# arduino_pir_sensor.net
KiCad netlist of a schematic drawn in EAGLE
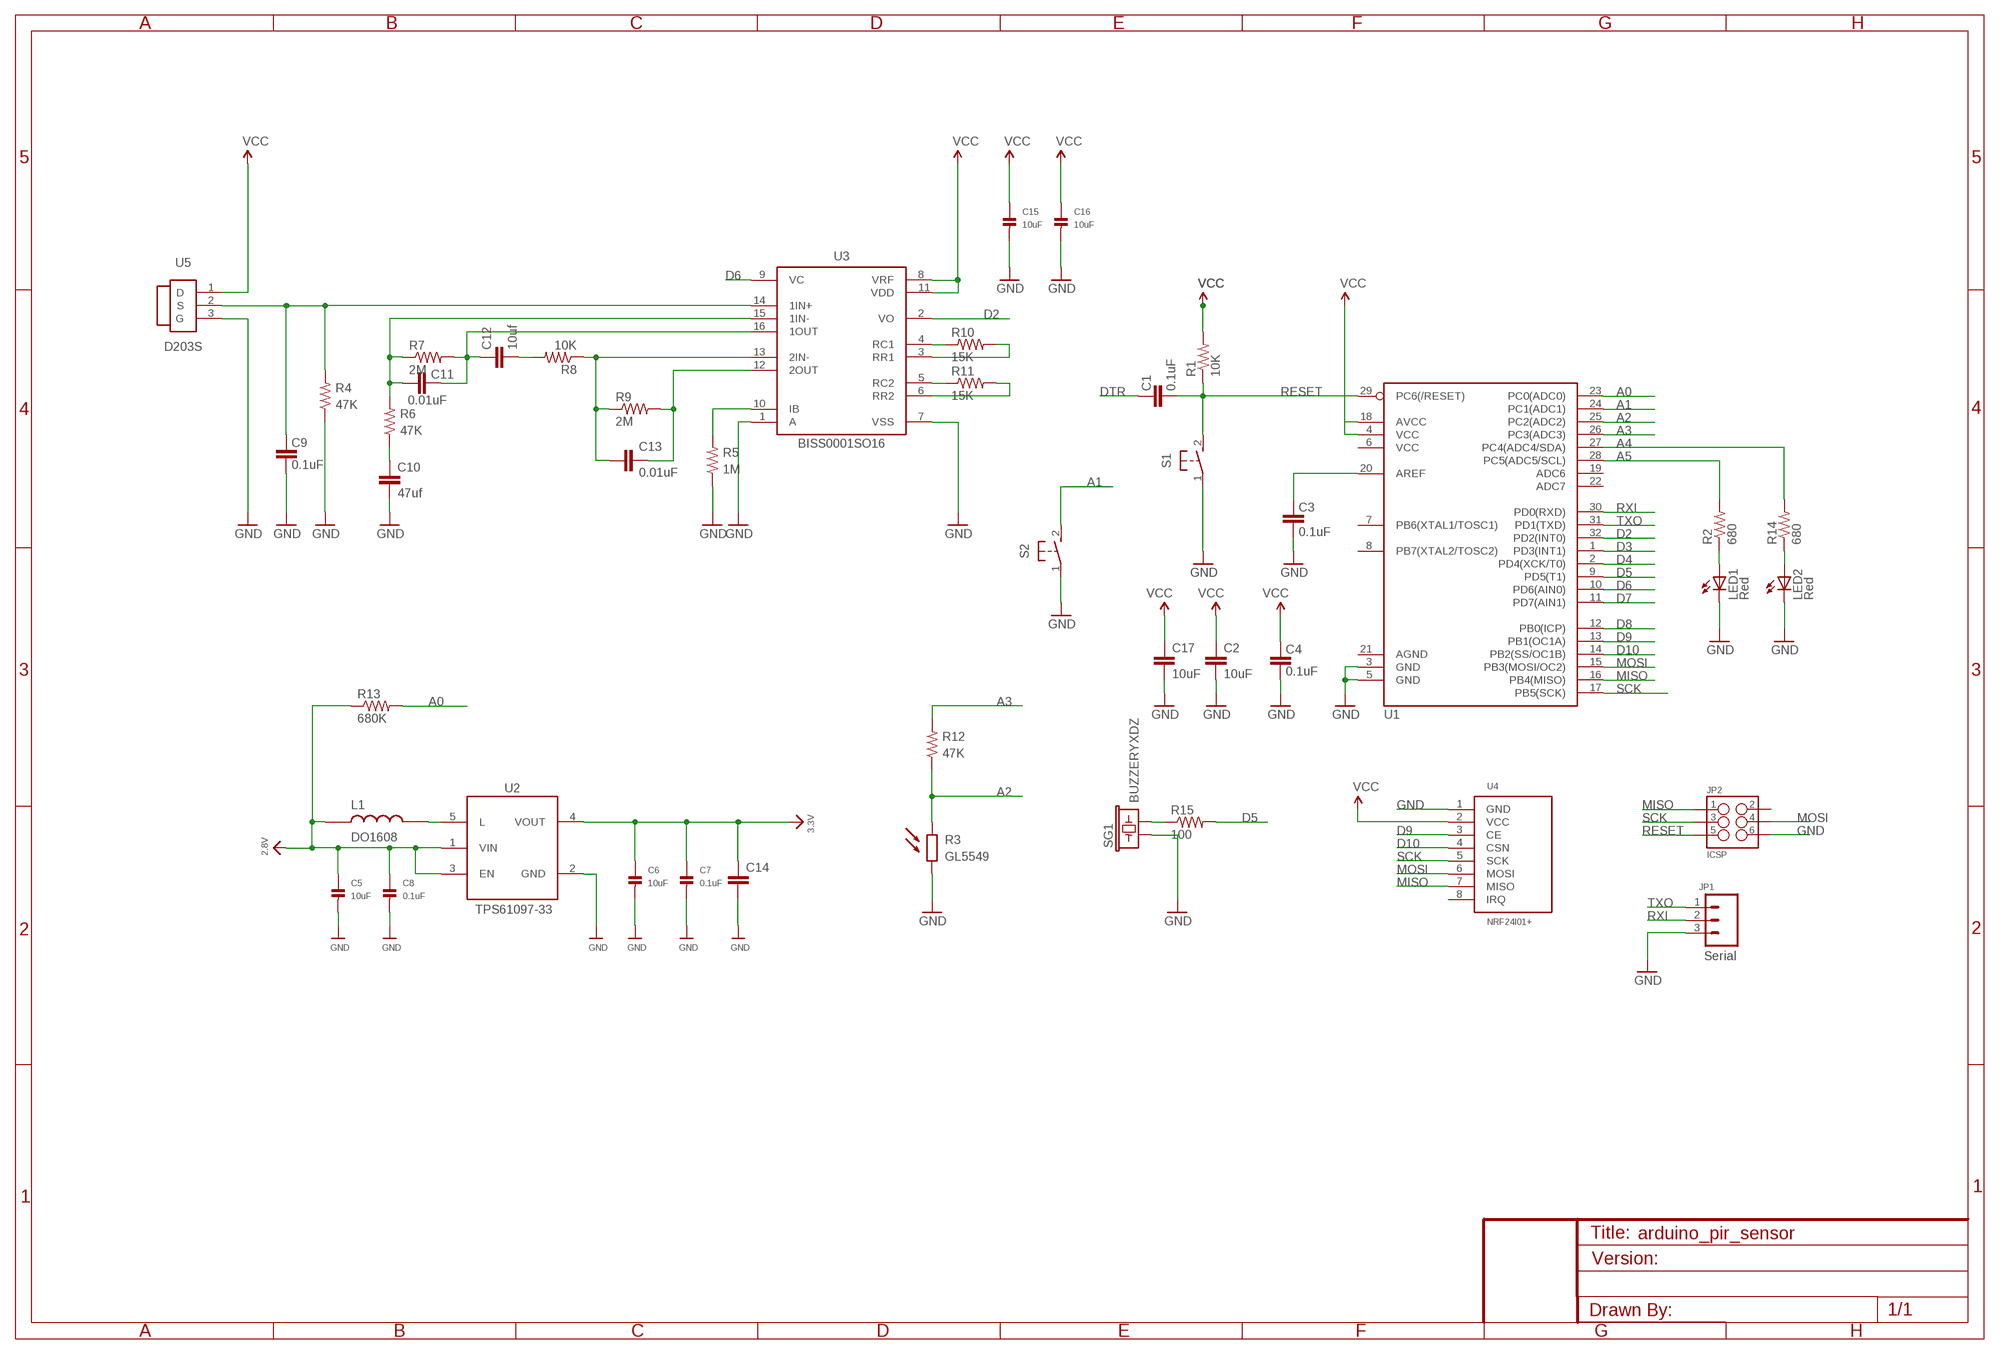
[diagram p0: schematic, sheet 1]

(export (version "E")
  (design (tool "Eeschema 10.0.6"))
  (components
    (comp (ref "C1")
      (value "0.1uF")
      (footprint "eagle-import:0603-CAP")
      (fields (field (name "MPN") "02016D104KAT2A"))
      (libsource (lib "eagle-import") (part "CAP0603-CAP"))
    )
    (comp (ref "C2")
      (value "10uF")
      (footprint "eagle-import:1206")
      (libsource (lib "eagle-import") (part "CAP1206"))
    )
    (comp (ref "C3")
      (value "0.1uF")
      (footprint "eagle-import:0603-CAP")
      (fields (field (name "MPN") "02016D104KAT2A"))
      (libsource (lib "eagle-import") (part "CAP0603-CAP"))
    )
    (comp (ref "C4")
      (value "0.1uF")
      (footprint "eagle-import:0603-CAP")
      (fields (field (name "MPN") "02016D104KAT2A"))
      (libsource (lib "eagle-import") (part "CAP0603-CAP"))
    )
    (comp (ref "C5")
      (value "10uF")
      (footprint "eagle-import:1206")
      (libsource (lib "eagle-import") (part "CAP_CERAMIC1206"))
    )
    (comp (ref "C6")
      (value "10uF")
      (footprint "eagle-import:1206")
      (libsource (lib "eagle-import") (part "CAP_CERAMIC1206"))
    )
    (comp (ref "C7")
      (value "0.1uF")
      (footprint "eagle-import:0603")
      (libsource (lib "eagle-import") (part "CAP_CERAMIC0603"))
    )
    (comp (ref "C8")
      (value "0.1uF")
      (footprint "eagle-import:0603")
      (libsource (lib "eagle-import") (part "CAP_CERAMIC0603"))
    )
    (comp (ref "C9")
      (value "0.1uF")
      (footprint "eagle-import:0603-CAP")
      (fields (field (name "MPN") "02016D104KAT2A"))
      (libsource (lib "eagle-import") (part "CAP0603-CAP"))
    )
    (comp (ref "C10")
      (value "47uf")
      (footprint "eagle-import:0805")
      (libsource (lib "eagle-import") (part "CAP0805"))
    )
    (comp (ref "C11")
      (value "0.01uF")
      (footprint "eagle-import:0603-CAP")
      (libsource (lib "eagle-import") (part "CAP0603-CAP"))
    )
    (comp (ref "C12")
      (value "10uf")
      (footprint "eagle-import:0805")
      (libsource (lib "eagle-import") (part "CAP0805"))
    )
    (comp (ref "C13")
      (value "0.01uF")
      (footprint "eagle-import:0603-CAP")
      (libsource (lib "eagle-import") (part "CAP0603-CAP"))
    )
    (comp (ref "C14")
      (value "CAPPTH")
      (footprint "eagle-import:CAP-PTH-SMALL")
      (libsource (lib "eagle-import") (part "CAPPTH"))
    )
    (comp (ref "C15")
      (value "10uF")
      (footprint "eagle-import:1206")
      (libsource (lib "eagle-import") (part "CAP_CERAMIC1206"))
    )
    (comp (ref "C16")
      (value "10uF")
      (footprint "eagle-import:1206")
      (libsource (lib "eagle-import") (part "CAP_CERAMIC1206"))
    )
    (comp (ref "C17")
      (value "10uF")
      (footprint "eagle-import:1206")
      (libsource (lib "eagle-import") (part "CAP1206"))
    )
    (comp (ref "JP1")
      (value "Serial")
      (footprint "eagle-import:1X03")
      (libsource (lib "eagle-import") (part "M03PTH"))
    )
    (comp (ref "JP2")
      (value "ICSP")
      (footprint "eagle-import:2X3_POGO")
      (libsource (lib "eagle-import") (part "M03X2POGO_PINS"))
    )
    (comp (ref "L1")
      (value "DO1608")
      (footprint "eagle-import:DO1608")
      (libsource (lib "eagle-import") (part "DO1608"))
    )
    (comp (ref "LED1")
      (value "Red")
      (footprint "eagle-import:LED-0603")
      (libsource (lib "eagle-import") (part "LED0603"))
    )
    (comp (ref "LED2")
      (value "Red")
      (footprint "eagle-import:LED5MM")
      (libsource (lib "eagle-import") (part "led_LED5MM"))
    )
    (comp (ref "R1")
      (value "10K")
      (footprint "eagle-import:0603-RES")
      (libsource (lib "eagle-import") (part "RESISTOR0603-RES"))
    )
    (comp (ref "R2")
      (value "680")
      (footprint "eagle-import:0603-RES")
      (libsource (lib "eagle-import") (part "RESISTOR0603-RES"))
    )
    (comp (ref "R3")
      (value "GL5549")
      (footprint "eagle-import:PHOTCELL")
      (libsource (lib "eagle-import") (part "GL5549"))
    )
    (comp (ref "R4")
      (value "47K")
      (footprint "eagle-import:0603-RES")
      (libsource (lib "eagle-import") (part "RESISTOR0603-RES"))
    )
    (comp (ref "R5")
      (value "1M")
      (footprint "eagle-import:0603-RES")
      (libsource (lib "eagle-import") (part "RESISTOR0603-RES"))
    )
    (comp (ref "R6")
      (value "47K")
      (footprint "eagle-import:0603-RES")
      (libsource (lib "eagle-import") (part "RESISTOR0603-RES"))
    )
    (comp (ref "R7")
      (value "2M")
      (footprint "eagle-import:0603-RES")
      (libsource (lib "eagle-import") (part "RESISTOR0603-RES"))
    )
    (comp (ref "R8")
      (value "10K")
      (footprint "eagle-import:0603-RES")
      (libsource (lib "eagle-import") (part "RESISTOR0603-RES"))
    )
    (comp (ref "R9")
      (value "2M")
      (footprint "eagle-import:0603-RES")
      (libsource (lib "eagle-import") (part "RESISTOR0603-RES"))
    )
    (comp (ref "R10")
      (value "15K")
      (footprint "eagle-import:0603-RES")
      (libsource (lib "eagle-import") (part "RESISTOR0603-RES"))
    )
    (comp (ref "R11")
      (value "15K")
      (footprint "eagle-import:0603-RES")
      (libsource (lib "eagle-import") (part "RESISTOR0603-RES"))
    )
    (comp (ref "R12")
      (value "47K")
      (footprint "eagle-import:0603-RES")
      (libsource (lib "eagle-import") (part "RESISTOR0603-RES"))
    )
    (comp (ref "R13")
      (value "680K")
      (footprint "eagle-import:0603-RES")
      (libsource (lib "eagle-import") (part "RESISTOR0603-RES"))
    )
    (comp (ref "R14")
      (value "680")
      (footprint "eagle-import:0603-RES")
      (libsource (lib "eagle-import") (part "RESISTOR0603-RES"))
    )
    (comp (ref "R15")
      (value "100")
      (footprint "eagle-import:0603-RES")
      (libsource (lib "eagle-import") (part "RESISTOR0603-RES"))
    )
    (comp (ref "S1")
      (value "TAC_SWITCH_SPST-6X3")
      (footprint "eagle-import:TACTILE_SMD_6X3")
      (libsource (lib "eagle-import") (part "TAC_SWITCH_SPST-6X3"))
    )
    (comp (ref "S2")
      (value "TAC_SWITCH_SPST-6X3")
      (footprint "eagle-import:TACTILE_SMD_6X3")
      (libsource (lib "eagle-import") (part "TAC_SWITCH_SPST-6X3"))
    )
    (comp (ref "SG1")
      (value "BUZZERYXDZ")
      (footprint "eagle-import:BUZZER-12MM-7.65")
      (libsource (lib "eagle-import") (part "BUZZERYXDZ"))
    )
    (comp (ref "U1")
      (value "ATMEGA328_SMT")
      (footprint "eagle-import:TQFP32-08")
      (libsource (lib "eagle-import") (part "ATMEGA328_SMT"))
    )
    (comp (ref "U2")
      (value "TPS61097-33")
      (footprint "eagle-import:SOT-23-5L")
      (libsource (lib "eagle-import") (part "TPS61097-33"))
    )
    (comp (ref "U3")
      (value "BISS0001SO16")
      (footprint "eagle-import:SO-16")
      (libsource (lib "eagle-import") (part "BISS0001SO16"))
    )
    (comp (ref "U4")
      (value "NRF24L01+_MODULE")
      (footprint "eagle-import:NRF24L01+MODULE")
      (libsource (lib "eagle-import") (part "NRF24L01+_MODULE"))
    )
    (comp (ref "U5")
      (value "D203S")
      (footprint "eagle-import:TO5")
      (libsource (lib "eagle-import") (part "D203S"))
    )
  )
  (nets
    (net (code "1") (name "/A0") (class "Default")
      (node (ref "R13") (pin "2") (pinfunction "2_2") (pintype "passive"))
      (node (ref "U1") (pin "23") (pinfunction "PC0(ADC0)_23") (pintype "bidirectional"))
    )
    (net (code "2") (name "/A1") (class "Default")
      (node (ref "S2") (pin "2") (pinfunction "2_2") (pintype "passive"))
      (node (ref "U1") (pin "24") (pinfunction "PC1(ADC1)_24") (pintype "bidirectional"))
    )
    (net (code "3") (name "/A2") (class "Default")
      (node (ref "R12") (pin "1") (pinfunction "1_1") (pintype "passive"))
      (node (ref "R3") (pin "P$1") (pinfunction "P$1_P$1") (pintype "bidirectional"))
      (node (ref "U1") (pin "25") (pinfunction "PC2(ADC2)_25") (pintype "bidirectional"))
    )
    (net (code "4") (name "/A3") (class "Default")
      (node (ref "R12") (pin "2") (pinfunction "2_2") (pintype "passive"))
      (node (ref "U1") (pin "26") (pinfunction "PC3(ADC3)_26") (pintype "bidirectional"))
    )
    (net (code "5") (name "/A4") (class "Default")
      (node (ref "R14") (pin "2") (pinfunction "2_2") (pintype "passive"))
      (node (ref "U1") (pin "27") (pinfunction "PC4(ADC4/SDA)_27") (pintype "bidirectional"))
    )
    (net (code "6") (name "/A5") (class "Default")
      (node (ref "R2") (pin "2") (pinfunction "2_2") (pintype "passive"))
      (node (ref "U1") (pin "28") (pinfunction "PC5(ADC5/SCL)_28") (pintype "bidirectional"))
    )
    (net (code "7") (name "/D2") (class "Default")
      (node (ref "U1") (pin "32") (pinfunction "PD2(INT0)_32") (pintype "bidirectional"))
      (node (ref "U3") (pin "2") (pinfunction "VO_2") (pintype "output"))
    )
    (net (code "8") (name "/D3") (class "Default")
      (node (ref "U1") (pin "1") (pinfunction "PD3(INT1)_1") (pintype "bidirectional"))
    )
    (net (code "9") (name "/D4") (class "Default")
      (node (ref "U1") (pin "2") (pinfunction "PD4(XCK/T0)_2") (pintype "bidirectional"))
    )
    (net (code "10") (name "/D5") (class "Default")
      (node (ref "R15") (pin "2") (pinfunction "2_2") (pintype "passive"))
      (node (ref "U1") (pin "9") (pinfunction "PD5(T1)_9") (pintype "bidirectional"))
    )
    (net (code "11") (name "/D6") (class "Default")
      (node (ref "U1") (pin "10") (pinfunction "PD6(AIN0)_10") (pintype "bidirectional"))
      (node (ref "U3") (pin "9") (pinfunction "VC_9") (pintype "input"))
    )
    (net (code "12") (name "/D7") (class "Default")
      (node (ref "U1") (pin "11") (pinfunction "PD7(AIN1)_11") (pintype "bidirectional"))
    )
    (net (code "13") (name "/D8") (class "Default")
      (node (ref "U1") (pin "12") (pinfunction "PB0(ICP)_12") (pintype "bidirectional"))
    )
    (net (code "14") (name "/D9") (class "Default")
      (node (ref "U1") (pin "13") (pinfunction "PB1(OC1A)_13") (pintype "bidirectional"))
      (node (ref "U4") (pin "3") (pinfunction "CE_3") (pintype "input"))
    )
    (net (code "15") (name "/D10") (class "Default")
      (node (ref "U1") (pin "14") (pinfunction "PB2(SS/OC1B)_14") (pintype "bidirectional"))
      (node (ref "U4") (pin "4") (pinfunction "CSN_4") (pintype "input"))
    )
    (net (code "16") (name "/DTR") (class "Default")
      (node (ref "C1") (pin "2") (pinfunction "2_2") (pintype "passive"))
    )
    (net (code "17") (name "/MISO") (class "Default")
      (node (ref "JP2") (pin "P$1") (pinfunction "1_P$1") (pintype "bidirectional"))
      (node (ref "U1") (pin "16") (pinfunction "PB4(MISO)_16") (pintype "bidirectional"))
      (node (ref "U4") (pin "7") (pinfunction "MISO_7") (pintype "output"))
    )
    (net (code "18") (name "/MOSI") (class "Default")
      (node (ref "JP2") (pin "P$4") (pinfunction "4_P$4") (pintype "bidirectional"))
      (node (ref "U1") (pin "15") (pinfunction "PB3(MOSI/OC2)_15") (pintype "bidirectional"))
      (node (ref "U4") (pin "6") (pinfunction "MOSI_6") (pintype "input"))
    )
    (net (code "19") (name "/RESET") (class "Default")
      (node (ref "C1") (pin "1") (pinfunction "1_1") (pintype "passive"))
      (node (ref "JP2") (pin "P$5") (pinfunction "5_P$5") (pintype "bidirectional"))
      (node (ref "R1") (pin "1") (pinfunction "1_1") (pintype "passive"))
      (node (ref "S1") (pin "2") (pinfunction "2_2") (pintype "passive"))
      (node (ref "U1") (pin "29") (pinfunction "PC6(/RESET)_29") (pintype "bidirectional"))
    )
    (net (code "20") (name "/RXI") (class "Default")
      (node (ref "JP1") (pin "2") (pinfunction "2_2") (pintype "passive"))
      (node (ref "U1") (pin "30") (pinfunction "PD0(RXD)_30") (pintype "bidirectional"))
    )
    (net (code "21") (name "/SCK") (class "Default")
      (node (ref "JP2") (pin "P$3") (pinfunction "3_P$3") (pintype "bidirectional"))
      (node (ref "U1") (pin "17") (pinfunction "PB5(SCK)_17") (pintype "bidirectional"))
      (node (ref "U4") (pin "5") (pinfunction "SCK_5") (pintype "input"))
    )
    (net (code "22") (name "/TXO") (class "Default")
      (node (ref "JP1") (pin "1") (pinfunction "1_1") (pintype "passive"))
      (node (ref "U1") (pin "31") (pinfunction "PD1(TXD)_31") (pintype "bidirectional"))
    )
    (net (code "23") (name "2.8V") (class "Default")
      (node (ref "C5") (pin "1") (pinfunction "P$1_1") (pintype "passive"))
      (node (ref "C8") (pin "1") (pinfunction "P$1_1") (pintype "passive"))
      (node (ref "L1") (pin "P$1") (pinfunction "1_P$1") (pintype "passive"))
      (node (ref "R13") (pin "1") (pinfunction "1_1") (pintype "passive"))
      (node (ref "U2") (pin "1") (pinfunction "VIN_1") (pintype "input"))
      (node (ref "U2") (pin "3") (pinfunction "EN_3") (pintype "input"))
    )
    (net (code "24") (name "3.3V") (class "Default")
      (node (ref "C14") (pin "1") (pinfunction "1_1") (pintype "passive"))
      (node (ref "C15") (pin "1") (pinfunction "P$1_1") (pintype "passive"))
      (node (ref "C16") (pin "1") (pinfunction "P$1_1") (pintype "passive"))
      (node (ref "C17") (pin "1") (pinfunction "1_1") (pintype "passive"))
      (node (ref "C2") (pin "1") (pinfunction "1_1") (pintype "passive"))
      (node (ref "C4") (pin "2") (pinfunction "2_2") (pintype "passive"))
      (node (ref "C6") (pin "1") (pinfunction "P$1_1") (pintype "passive"))
      (node (ref "C7") (pin "1") (pinfunction "P$1_1") (pintype "passive"))
      (node (ref "R1") (pin "2") (pinfunction "2_2") (pintype "passive"))
      (node (ref "U1") (pin "18") (pinfunction "AVCC_18") (pintype "bidirectional"))
      (node (ref "U1") (pin "4") (pinfunction "VCC_4") (pintype "bidirectional"))
      (node (ref "U2") (pin "4") (pinfunction "VOUT_4") (pintype "output"))
      (node (ref "U3") (pin "11") (pinfunction "VDD_11") (pintype "power_in"))
      (node (ref "U3") (pin "8") (pinfunction "VRF_8") (pintype "input"))
      (node (ref "U4") (pin "2") (pinfunction "VCC_2") (pintype "power_in"))
      (node (ref "U5") (pin "1") (pinfunction "D_1") (pintype "power_in"))
    )
    (net (code "25") (name "GND") (class "Default")
      (node (ref "C10") (pin "2") (pinfunction "2_2") (pintype "passive"))
      (node (ref "C14") (pin "2") (pinfunction "2_2") (pintype "passive"))
      (node (ref "C15") (pin "2") (pinfunction "P$2_2") (pintype "passive"))
      (node (ref "C16") (pin "2") (pinfunction "P$2_2") (pintype "passive"))
      (node (ref "C17") (pin "2") (pinfunction "2_2") (pintype "passive"))
      (node (ref "C2") (pin "2") (pinfunction "2_2") (pintype "passive"))
      (node (ref "C3") (pin "1") (pinfunction "1_1") (pintype "passive"))
      (node (ref "C4") (pin "1") (pinfunction "1_1") (pintype "passive"))
      (node (ref "C5") (pin "2") (pinfunction "P$2_2") (pintype "passive"))
      (node (ref "C6") (pin "2") (pinfunction "P$2_2") (pintype "passive"))
      (node (ref "C7") (pin "2") (pinfunction "P$2_2") (pintype "passive"))
      (node (ref "C8") (pin "2") (pinfunction "P$2_2") (pintype "passive"))
      (node (ref "C9") (pin "1") (pinfunction "1_1") (pintype "passive"))
      (node (ref "JP1") (pin "3") (pinfunction "3_3") (pintype "passive"))
      (node (ref "JP2") (pin "P$6") (pinfunction "6_P$6") (pintype "bidirectional"))
      (node (ref "LED1") (pin "C") (pinfunction "C_C") (pintype "passive"))
      (node (ref "LED2") (pin "K") (pinfunction "C_K") (pintype "passive"))
      (node (ref "R3") (pin "P$2") (pinfunction "P$2_P$2") (pintype "bidirectional"))
      (node (ref "R4") (pin "1") (pinfunction "1_1") (pintype "passive"))
      (node (ref "R5") (pin "1") (pinfunction "1_1") (pintype "passive"))
      (node (ref "S1") (pin "1") (pinfunction "1_1") (pintype "passive"))
      (node (ref "S2") (pin "1") (pinfunction "1_1") (pintype "passive"))
      (node (ref "SG1") (pin "-") (pinfunction "2_-") (pintype "passive"))
      (node (ref "U1") (pin "3") (pinfunction "GND_3") (pintype "bidirectional"))
      (node (ref "U1") (pin "5") (pinfunction "GND_5") (pintype "bidirectional"))
      (node (ref "U2") (pin "2") (pinfunction "GND_2") (pintype "power_in"))
      (node (ref "U3") (pin "1") (pinfunction "A_1") (pintype "input"))
      (node (ref "U3") (pin "7") (pinfunction "VSS_7") (pintype "power_in"))
      (node (ref "U4") (pin "1") (pinfunction "GND_1") (pintype "power_in"))
      (node (ref "U5") (pin "3") (pinfunction "G_3") (pintype "power_in"))
    )
    (net (code "26") (name "Net-(C10-Pad1)") (class "Default")
      (node (ref "C10") (pin "1") (pinfunction "1_1") (pintype "passive"))
      (node (ref "R6") (pin "1") (pinfunction "1_1") (pintype "passive"))
    )
    (net (code "27") (name "Net-(C12-Pad2)") (class "Default")
      (node (ref "C12") (pin "2") (pinfunction "2_2") (pintype "passive"))
      (node (ref "R8") (pin "2") (pinfunction "2_2") (pintype "passive"))
    )
    (net (code "28") (name "Net-(L1-2)") (class "Default")
      (node (ref "L1") (pin "P$2") (pinfunction "2_P$2") (pintype "passive"))
      (node (ref "U2") (pin "5") (pinfunction "L_5") (pintype "bidirectional"))
    )
    (net (code "29") (name "Net-(LED1-PadA)") (class "Default")
      (node (ref "LED1") (pin "A") (pinfunction "A_A") (pintype "passive"))
      (node (ref "R2") (pin "1") (pinfunction "1_1") (pintype "passive"))
    )
    (net (code "30") (name "Net-(LED2-PadA)") (class "Default")
      (node (ref "LED2") (pin "A") (pinfunction "A_A") (pintype "passive"))
      (node (ref "R14") (pin "1") (pinfunction "1_1") (pintype "passive"))
    )
    (net (code "31") (name "Net-(SG1-1)") (class "Default")
      (node (ref "R15") (pin "1") (pinfunction "1_1") (pintype "passive"))
      (node (ref "SG1") (pin "+") (pinfunction "1_+") (pintype "passive"))
    )
    (net (code "32") (name "Net-(U1-AREF)") (class "Default")
      (node (ref "C3") (pin "2") (pinfunction "2_2") (pintype "passive"))
      (node (ref "U1") (pin "20") (pinfunction "AREF_20") (pintype "bidirectional"))
    )
    (net (code "33") (name "Net-(U3-1IN+)") (class "Default")
      (node (ref "C9") (pin "2") (pinfunction "2_2") (pintype "passive"))
      (node (ref "R4") (pin "2") (pinfunction "2_2") (pintype "passive"))
      (node (ref "U3") (pin "14") (pinfunction "1IN+_14") (pintype "input"))
      (node (ref "U5") (pin "2") (pinfunction "S_2") (pintype "output"))
    )
    (net (code "34") (name "Net-(U3-1IN-)") (class "Default")
      (node (ref "C11") (pin "2") (pinfunction "2_2") (pintype "passive"))
      (node (ref "R6") (pin "2") (pinfunction "2_2") (pintype "passive"))
      (node (ref "R7") (pin "1") (pinfunction "1_1") (pintype "passive"))
      (node (ref "U3") (pin "15") (pinfunction "1IN-_15") (pintype "input"))
    )
    (net (code "35") (name "Net-(U3-1OUT)") (class "Default")
      (node (ref "C11") (pin "1") (pinfunction "1_1") (pintype "passive"))
      (node (ref "C12") (pin "1") (pinfunction "1_1") (pintype "passive"))
      (node (ref "R7") (pin "2") (pinfunction "2_2") (pintype "passive"))
      (node (ref "U3") (pin "16") (pinfunction "1OUT_16") (pintype "output"))
    )
    (net (code "36") (name "Net-(U3-2IN-)") (class "Default")
      (node (ref "C13") (pin "1") (pinfunction "1_1") (pintype "passive"))
      (node (ref "R8") (pin "1") (pinfunction "1_1") (pintype "passive"))
      (node (ref "R9") (pin "1") (pinfunction "1_1") (pintype "passive"))
      (node (ref "U3") (pin "13") (pinfunction "2IN-_13") (pintype "input"))
    )
    (net (code "37") (name "Net-(U3-2OUT)") (class "Default")
      (node (ref "C13") (pin "2") (pinfunction "2_2") (pintype "passive"))
      (node (ref "R9") (pin "2") (pinfunction "2_2") (pintype "passive"))
      (node (ref "U3") (pin "12") (pinfunction "2OUT_12") (pintype "output"))
    )
    (net (code "38") (name "Net-(U3-IB)") (class "Default")
      (node (ref "R5") (pin "2") (pinfunction "2_2") (pintype "passive"))
      (node (ref "U3") (pin "10") (pinfunction "IB_10") (pintype "input"))
    )
    (net (code "39") (name "Net-(U3-RC1)") (class "Default")
      (node (ref "R10") (pin "1") (pinfunction "1_1") (pintype "passive"))
      (node (ref "U3") (pin "4") (pinfunction "RC1_4") (pintype "bidirectional"))
    )
    (net (code "40") (name "Net-(U3-RC2)") (class "Default")
      (node (ref "R11") (pin "1") (pinfunction "1_1") (pintype "passive"))
      (node (ref "U3") (pin "5") (pinfunction "RC2_5") (pintype "bidirectional"))
    )
    (net (code "41") (name "Net-(U3-RR1)") (class "Default")
      (node (ref "R10") (pin "2") (pinfunction "2_2") (pintype "passive"))
      (node (ref "U3") (pin "3") (pinfunction "RR1_3") (pintype "bidirectional"))
    )
    (net (code "42") (name "Net-(U3-RR2)") (class "Default")
      (node (ref "R11") (pin "2") (pinfunction "2_2") (pintype "passive"))
      (node (ref "U3") (pin "6") (pinfunction "RR2_6") (pintype "bidirectional"))
    )
    (net (code "43") (name "unconnected-(JP2-2-PadP$2)") (class "Default")
      (node (ref "JP2") (pin "P$2") (pinfunction "2_P$2") (pintype "bidirectional"))
    )
    (net (code "44") (name "unconnected-(U1-ADC6-Pad19)") (class "Default")
      (node (ref "U1") (pin "19") (pinfunction "ADC6_19") (pintype "bidirectional"))
    )
    (net (code "45") (name "unconnected-(U1-ADC7-Pad22)") (class "Default")
      (node (ref "U1") (pin "22") (pinfunction "ADC7_22") (pintype "bidirectional"))
    )
    (net (code "46") (name "unconnected-(U1-AGND-Pad21)") (class "Default")
      (node (ref "U1") (pin "21") (pinfunction "AGND_21") (pintype "bidirectional"))
    )
    (net (code "47") (name "unconnected-(U1-PB6(XTAL1{slash}TOSC1)-Pad7)") (class "Default")
      (node (ref "U1") (pin "7") (pinfunction "PB6(XTAL1/TOSC1)_7") (pintype "bidirectional"))
    )
    (net (code "48") (name "unconnected-(U1-PB7(XTAL2{slash}TOSC2)-Pad8)") (class "Default")
      (node (ref "U1") (pin "8") (pinfunction "PB7(XTAL2/TOSC2)_8") (pintype "bidirectional"))
    )
    (net (code "49") (name "unconnected-(U1-VCC-Pad6)") (class "Default")
      (node (ref "U1") (pin "6") (pinfunction "VCC_6") (pintype "bidirectional"))
    )
    (net (code "50") (name "unconnected-(U4-IRQ-Pad8)") (class "Default")
      (node (ref "U4") (pin "8") (pinfunction "IRQ_8") (pintype "output"))
    )
  )
)
